# Shock_Controller.net
KiCad netlist of a schematic drawn in EAGLE
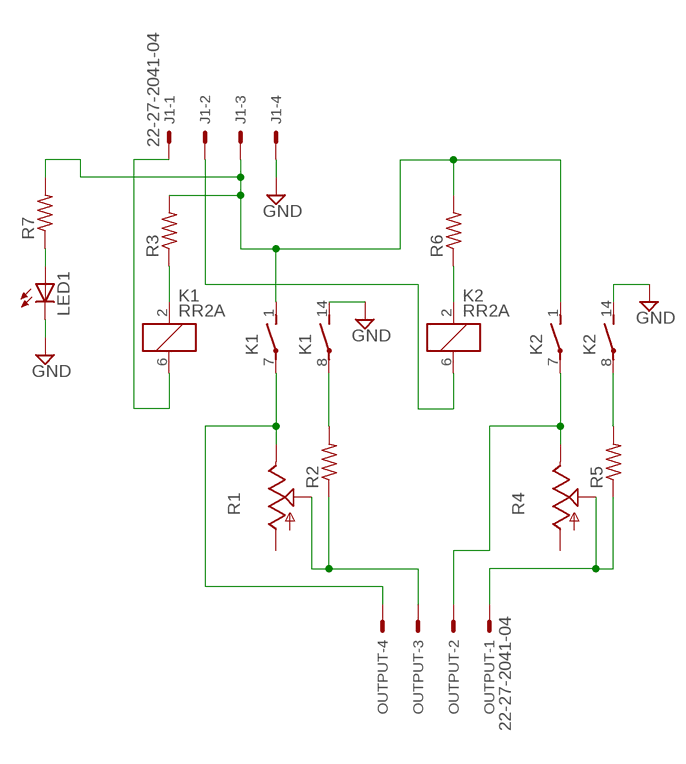
[diagram p0: schematic, sheet 1]

(export (version "E")
  (design (tool "Eeschema 10.0.6"))
  (components
    (comp (ref "J1")
      (value "22-27-2041-04")
      (footprint "eagle-import:6410-04")
      (libsource (lib "eagle-import") (part "22-?-0427-2041"))
    )
    (comp (ref "K1")
      (value "RR2A")
      (footprint "eagle-import:RR2A")
      (libsource (lib "eagle-import") (part "RR2A"))
    )
    (comp (ref "K2")
      (value "RR2A")
      (footprint "eagle-import:RR2A")
      (libsource (lib "eagle-import") (part "RR2A"))
    )
    (comp (ref "LED1")
      (value "LEDSFH482")
      (footprint "eagle-import:SFH482")
      (libsource (lib "eagle-import") (part "LEDSFH482"))
    )
    (comp (ref "OUTPUT")
      (value "22-27-2041-04")
      (footprint "eagle-import:6410-04")
      (libsource (lib "eagle-import") (part "22-?-0427-2041"))
    )
    (comp (ref "R1")
      (value "TRIM_US-SP19L")
      (footprint "eagle-import:SP19L")
      (libsource (lib "eagle-import") (part "TRIM_US-SP19L"))
    )
    (comp (ref "R2")
      (value "R-US_0207/2V")
      (footprint "eagle-import:0207_2V")
      (libsource (lib "eagle-import") (part "R-US_0207/2V"))
    )
    (comp (ref "R3")
      (value "R-US_0207/2V")
      (footprint "eagle-import:0207_2V")
      (libsource (lib "eagle-import") (part "R-US_0207/2V"))
    )
    (comp (ref "R4")
      (value "TRIM_US-SP19L")
      (footprint "eagle-import:SP19L")
      (libsource (lib "eagle-import") (part "TRIM_US-SP19L"))
    )
    (comp (ref "R5")
      (value "R-US_0207/2V")
      (footprint "eagle-import:0207_2V")
      (libsource (lib "eagle-import") (part "R-US_0207/2V"))
    )
    (comp (ref "R6")
      (value "R-US_0207/2V")
      (footprint "eagle-import:0207_2V")
      (libsource (lib "eagle-import") (part "R-US_0207/2V"))
    )
    (comp (ref "R7")
      (value "R-US_0207/2V")
      (footprint "eagle-import:0207_2V")
      (libsource (lib "eagle-import") (part "R-US_0207/2V"))
    )
  )
  (nets
    (net (code "1") (name "GND") (class "Default")
      (node (ref "J1") (pin "4") (pinfunction "S_4") (pintype "passive"))
      (node (ref "K1") (pin "14") (pinfunction "S_14") (pintype "passive"))
      (node (ref "K2") (pin "14") (pinfunction "S_14") (pintype "passive"))
      (node (ref "LED1") (pin "K") (pinfunction "C_K") (pintype "passive"))
    )
    (net (code "2") (name "Net-(J1A-S)") (class "Default")
      (node (ref "J1") (pin "1") (pinfunction "S_1") (pintype "passive"))
      (node (ref "K1") (pin "6") (pinfunction "2_6") (pintype "passive"))
    )
    (net (code "3") (name "Net-(J1B-S)") (class "Default")
      (node (ref "J1") (pin "2") (pinfunction "S_2") (pintype "passive"))
      (node (ref "K2") (pin "6") (pinfunction "2_6") (pintype "passive"))
    )
    (net (code "4") (name "Net-(J1C-S)") (class "Default")
      (node (ref "J1") (pin "3") (pinfunction "S_3") (pintype "passive"))
      (node (ref "K1") (pin "1") (pinfunction "S_1") (pintype "passive"))
      (node (ref "K2") (pin "1") (pinfunction "S_1") (pintype "passive"))
      (node (ref "R3") (pin "2") (pinfunction "2_2") (pintype "passive"))
      (node (ref "R6") (pin "2") (pinfunction "2_2") (pintype "passive"))
      (node (ref "R7") (pin "2") (pinfunction "2_2") (pintype "passive"))
    )
    (net (code "5") (name "Net-(K1A-1)") (class "Default")
      (node (ref "K1") (pin "2") (pinfunction "1_2") (pintype "passive"))
      (node (ref "R3") (pin "1") (pinfunction "1_1") (pintype "passive"))
    )
    (net (code "6") (name "Net-(K1B-P)") (class "Default")
      (node (ref "K1") (pin "7") (pinfunction "P_7") (pintype "passive"))
      (node (ref "OUTPUT") (pin "4") (pinfunction "S_4") (pintype "passive"))
      (node (ref "R1") (pin "E") (pinfunction "E_E") (pintype "passive"))
    )
    (net (code "7") (name "Net-(K1C-P)") (class "Default")
      (node (ref "K1") (pin "8") (pinfunction "P_8") (pintype "passive"))
      (node (ref "R2") (pin "2") (pinfunction "2_2") (pintype "passive"))
    )
    (net (code "8") (name "Net-(K2A-1)") (class "Default")
      (node (ref "K2") (pin "2") (pinfunction "1_2") (pintype "passive"))
      (node (ref "R6") (pin "1") (pinfunction "1_1") (pintype "passive"))
    )
    (net (code "9") (name "Net-(K2B-P)") (class "Default")
      (node (ref "K2") (pin "7") (pinfunction "P_7") (pintype "passive"))
      (node (ref "OUTPUT") (pin "2") (pinfunction "S_2") (pintype "passive"))
      (node (ref "R4") (pin "E") (pinfunction "E_E") (pintype "passive"))
    )
    (net (code "10") (name "Net-(K2C-P)") (class "Default")
      (node (ref "K2") (pin "8") (pinfunction "P_8") (pintype "passive"))
      (node (ref "R5") (pin "2") (pinfunction "2_2") (pintype "passive"))
    )
    (net (code "11") (name "Net-(LED1-PadA)") (class "Default")
      (node (ref "LED1") (pin "A") (pinfunction "A_A") (pintype "passive"))
      (node (ref "R7") (pin "1") (pinfunction "1_1") (pintype "passive"))
    )
    (net (code "12") (name "Net-(OUTPUTA-S)") (class "Default")
      (node (ref "OUTPUT") (pin "1") (pinfunction "S_1") (pintype "passive"))
      (node (ref "R4") (pin "S") (pinfunction "S_S") (pintype "passive"))
      (node (ref "R5") (pin "1") (pinfunction "1_1") (pintype "passive"))
    )
    (net (code "13") (name "Net-(OUTPUTC-S)") (class "Default")
      (node (ref "OUTPUT") (pin "3") (pinfunction "S_3") (pintype "passive"))
      (node (ref "R1") (pin "S") (pinfunction "S_S") (pintype "passive"))
      (node (ref "R2") (pin "1") (pinfunction "1_1") (pintype "passive"))
    )
    (net (code "14") (name "unconnected-(R1-PadA)") (class "Default")
      (node (ref "R1") (pin "A") (pinfunction "A_A") (pintype "passive"))
    )
    (net (code "15") (name "unconnected-(R4-PadA)") (class "Default")
      (node (ref "R4") (pin "A") (pinfunction "A_A") (pintype "passive"))
    )
  )
)
